# Peripherals.net
KiCad netlist of a schematic drawn in Altium Designer
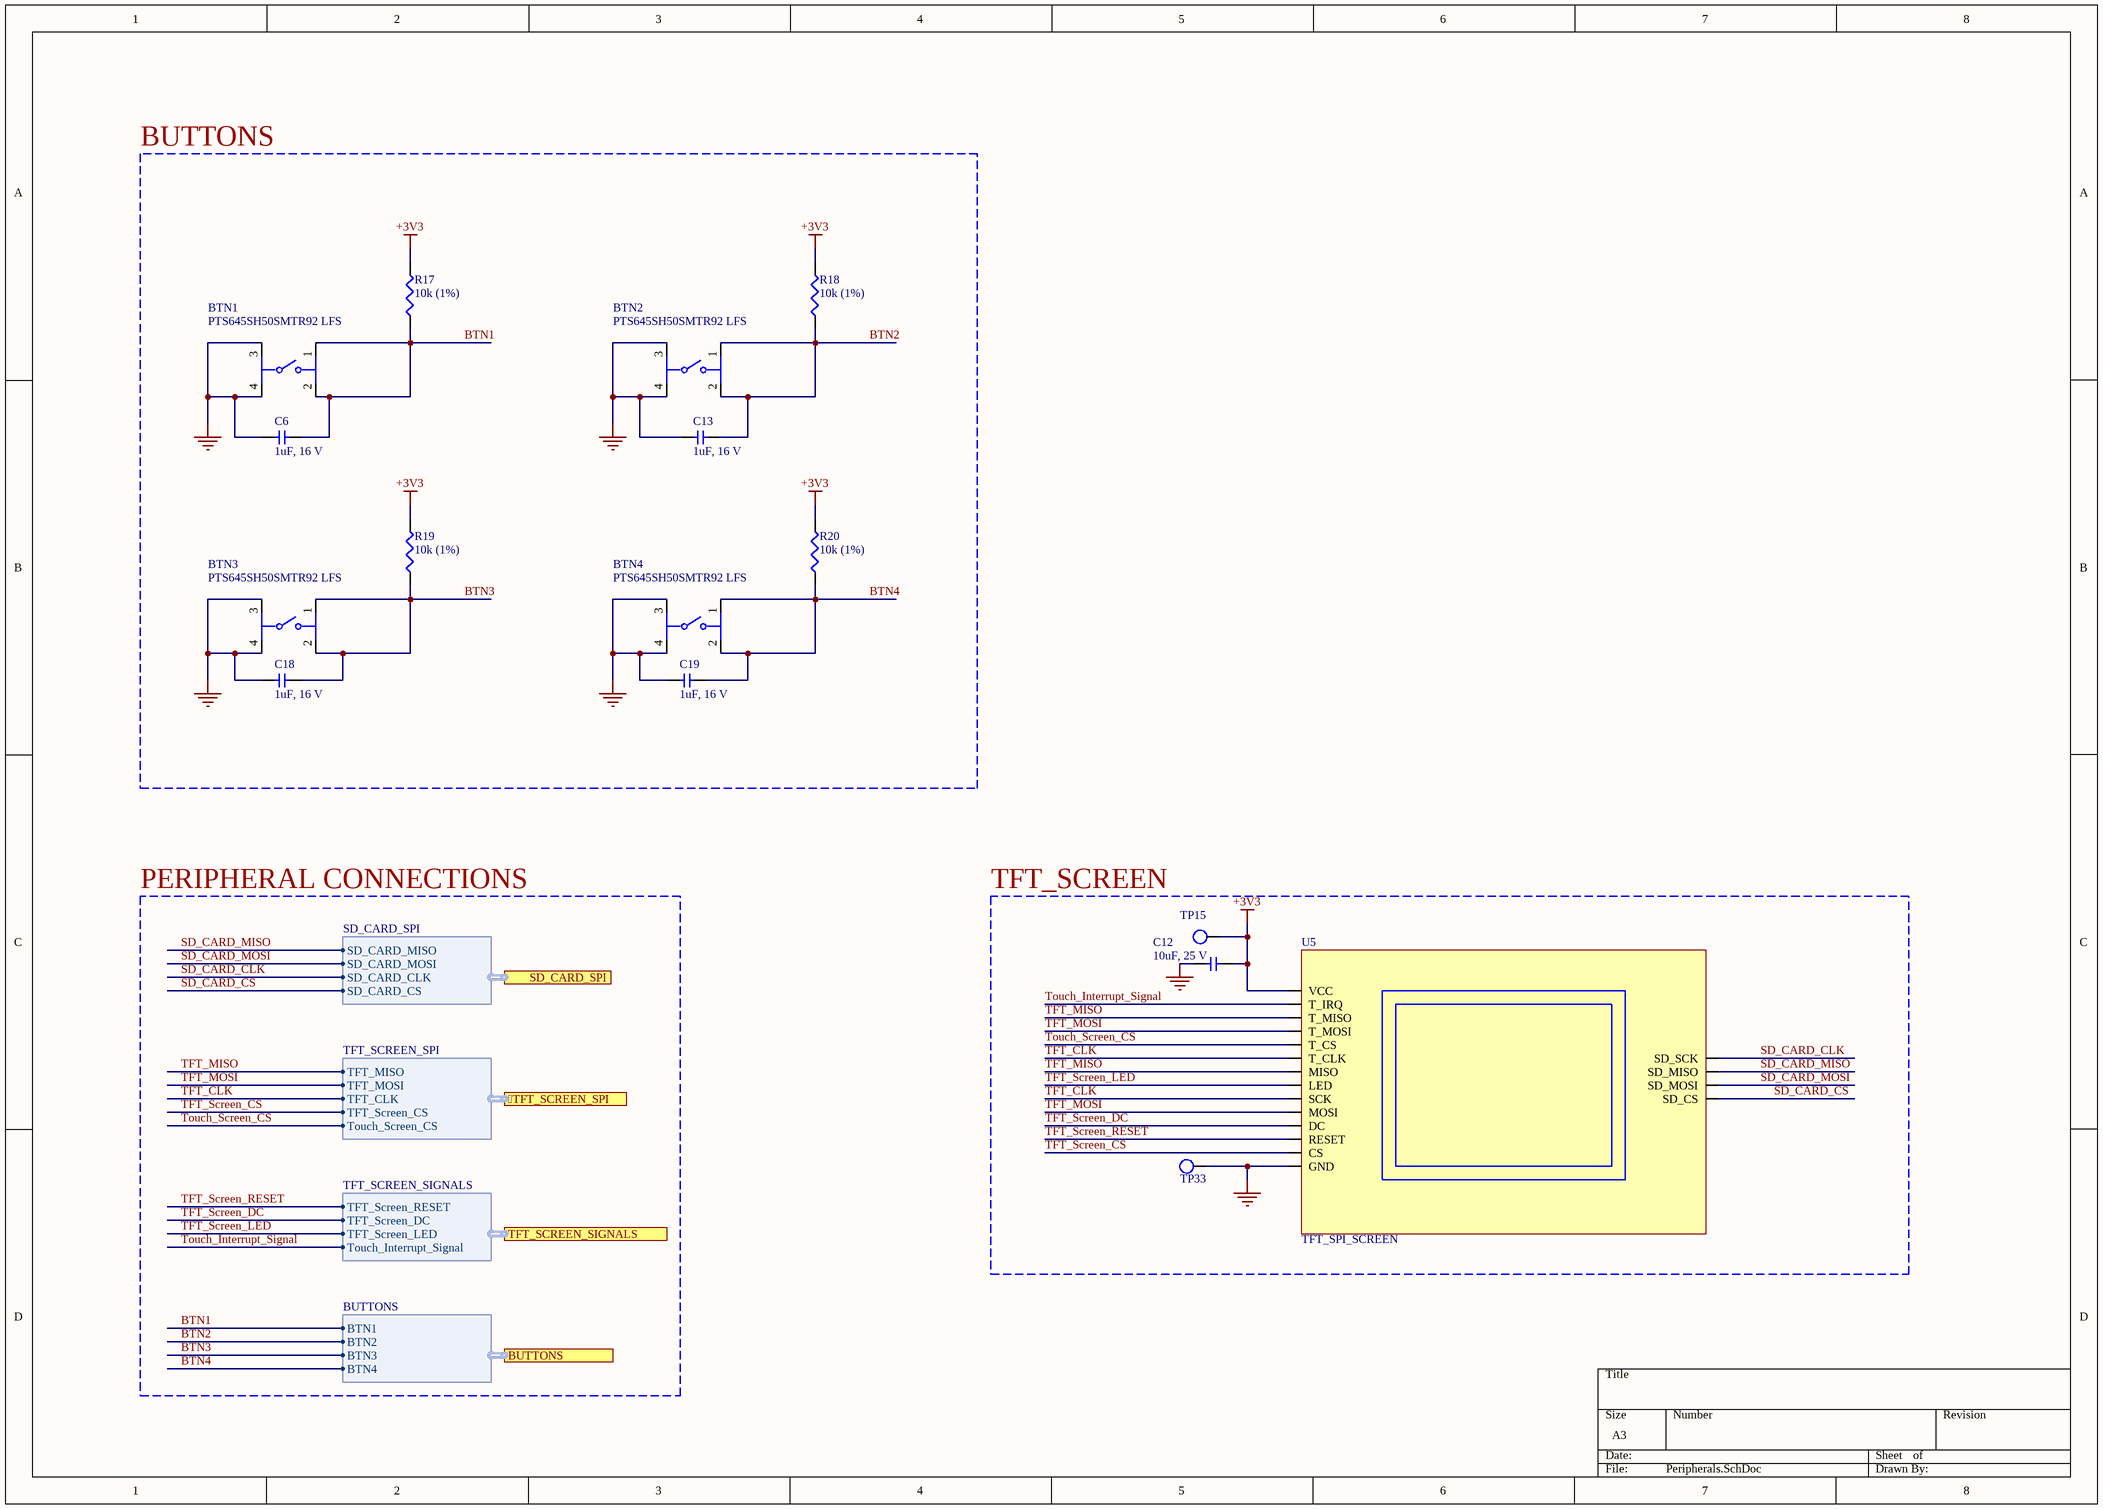
[diagram p0: Peripherals.SchDoc]

(export (version "E")
  (design (tool "Eeschema 10.0.6"))
  (components
    (comp (ref "BTN1")
      (value "PTS645SH50SMTR92 LFS")
      (footprint "FP-PTS645SH50SMTR92LFS-MFG")
      (description "Tactile Switch SPST-NO Top Actuated Surface Mount")
      (libsource (lib "SchLib") (part "PTS645SH50SMTR92 LFS"))
    )
    (comp (ref "BTN2")
      (value "PTS645SH50SMTR92 LFS")
      (footprint "FP-PTS645SH50SMTR92LFS-MFG")
      (description "Tactile Switch SPST-NO Top Actuated Surface Mount")
      (libsource (lib "SchLib") (part "PTS645SH50SMTR92 LFS"))
    )
    (comp (ref "BTN3")
      (value "PTS645SH50SMTR92 LFS")
      (footprint "FP-PTS645SH50SMTR92LFS-MFG")
      (description "Tactile Switch SPST-NO Top Actuated Surface Mount")
      (libsource (lib "SchLib") (part "PTS645SH50SMTR92 LFS"))
    )
    (comp (ref "BTN4")
      (value "PTS645SH50SMTR92 LFS")
      (footprint "FP-PTS645SH50SMTR92LFS-MFG")
      (description "Tactile Switch SPST-NO Top Actuated Surface Mount")
      (libsource (lib "SchLib") (part "PTS645SH50SMTR92 LFS"))
    )
    (comp (ref "C6")
      (value "1uF, 16 V")
      (footprint "0805_CAP")
      (libsource (lib "SchLib") (part "CL31B105KOFNNNE"))
    )
    (comp (ref "C12")
      (value "10uF, 25 V")
      (footprint "0805_CAP")
      (fields
        (field (name "MANUFACTURER") "Taiyo Yuden")
        (field (name "MANUFACTURER PART NUMBER") "TMK316BJ106KL-T")
      )
      (libsource (lib "SchLib") (part "TMK316BJ106KL-T"))
    )
    (comp (ref "C13")
      (value "1uF, 16 V")
      (footprint "0805_CAP")
      (libsource (lib "SchLib") (part "CL31B105KOFNNNE"))
    )
    (comp (ref "C18")
      (value "1uF, 16 V")
      (footprint "0805_CAP")
      (libsource (lib "SchLib") (part "CL31B105KOFNNNE"))
    )
    (comp (ref "C19")
      (value "1uF, 16 V")
      (footprint "0805_CAP")
      (libsource (lib "SchLib") (part "CL31B105KOFNNNE"))
    )
    (comp (ref "R17")
      (value "10k (1%)")
      (footprint "0805_Resistor")
      (fields (field (name "TOLERANCE") "1%"))
      (libsource (lib "SchLib") (part "RMCF0805FT10K0"))
    )
    (comp (ref "R18")
      (value "10k (1%)")
      (footprint "0805_Resistor")
      (fields (field (name "TOLERANCE") "1%"))
      (libsource (lib "SchLib") (part "RMCF0805FT10K0"))
    )
    (comp (ref "R19")
      (value "10k (1%)")
      (footprint "0805_Resistor")
      (fields (field (name "TOLERANCE") "1%"))
      (libsource (lib "SchLib") (part "RMCF0805FT10K0"))
    )
    (comp (ref "R20")
      (value "10k (1%)")
      (footprint "0805_Resistor")
      (fields (field (name "TOLERANCE") "1%"))
      (libsource (lib "SchLib") (part "RMCF0805FT10K0"))
    )
    (comp (ref "TP15")
      (value "Test Point")
      (footprint "Probe-Point")
      (description "Generic Test Point")
      (libsource (lib "University of Calgary Solar Car Team") (part "Test Point-Symbol-1"))
    )
    (comp (ref "TP33")
      (value "Test Point")
      (footprint "Probe-Point")
      (description "Generic Test Point")
      (libsource (lib "University of Calgary Solar Car Team") (part "Test Point-Symbol-1"))
    )
    (comp (ref "U5")
      (value "TFT_SPI_SCREEN")
      (footprint "TFT_SCREEN")
      (description "3.5inch SPI Module ILI9488 SKU:MSP3520")
      (libsource (lib "SchLib") (part "TFT_SPI_SCREEN"))
    )
  )
  (nets
    (net (code "5") (name "+3V3") (class "Default")
      (node (ref "C12") (pin "1") (pinfunction "1_1") (pintype "passive"))
      (node (ref "R17") (pin "2") (pinfunction "2_2") (pintype "passive"))
      (node (ref "R18") (pin "2") (pinfunction "2_2") (pintype "passive"))
      (node (ref "R19") (pin "2") (pinfunction "2_2") (pintype "passive"))
      (node (ref "R20") (pin "2") (pinfunction "2_2") (pintype "passive"))
      (node (ref "TP15") (pin "1") (pinfunction "1_1") (pintype "passive"))
      (node (ref "U5") (pin "1") (pinfunction "VCC_1") (pintype "passive"))
    )
    (net (code "6") (name "/BTN1") (class "Default")
      (node (ref "BTN1") (pin "1") (pinfunction "1_1") (pintype "passive"))
      (node (ref "BTN1") (pin "2") (pinfunction "2_2") (pintype "passive"))
      (node (ref "C6") (pin "2") (pinfunction "2_2") (pintype "passive"))
      (node (ref "R17") (pin "1") (pinfunction "1_1") (pintype "passive"))
    )
    (net (code "7") (name "/BTN2") (class "Default")
      (node (ref "BTN2") (pin "1") (pinfunction "1_1") (pintype "passive"))
      (node (ref "BTN2") (pin "2") (pinfunction "2_2") (pintype "passive"))
      (node (ref "C13") (pin "2") (pinfunction "2_2") (pintype "passive"))
      (node (ref "R18") (pin "1") (pinfunction "1_1") (pintype "passive"))
    )
    (net (code "8") (name "/BTN3") (class "Default")
      (node (ref "BTN3") (pin "1") (pinfunction "1_1") (pintype "passive"))
      (node (ref "BTN3") (pin "2") (pinfunction "2_2") (pintype "passive"))
      (node (ref "C18") (pin "2") (pinfunction "2_2") (pintype "passive"))
      (node (ref "R19") (pin "1") (pinfunction "1_1") (pintype "passive"))
    )
    (net (code "9") (name "/BTN4") (class "Default")
      (node (ref "BTN4") (pin "1") (pinfunction "1_1") (pintype "passive"))
      (node (ref "BTN4") (pin "2") (pinfunction "2_2") (pintype "passive"))
      (node (ref "C19") (pin "2") (pinfunction "2_2") (pintype "passive"))
      (node (ref "R20") (pin "1") (pinfunction "1_1") (pintype "passive"))
    )
    (net (code "10") (name "/SD_CARD_CLK") (class "Default")
      (node (ref "U5") (pin "18") (pinfunction "SD_SCK_18") (pintype "passive"))
    )
    (net (code "11") (name "/SD_CARD_CS") (class "Default")
      (node (ref "U5") (pin "15") (pinfunction "SD_CS_15") (pintype "passive"))
    )
    (net (code "12") (name "/SD_CARD_MISO") (class "Default")
      (node (ref "U5") (pin "17") (pinfunction "SD_MISO_17") (pintype "passive"))
    )
    (net (code "13") (name "/SD_CARD_MOSI") (class "Default")
      (node (ref "U5") (pin "16") (pinfunction "SD_MOSI_16") (pintype "passive"))
    )
    (net (code "14") (name "/TFT_CLK") (class "Default")
      (node (ref "U5") (pin "10") (pinfunction "T_CLK_10") (pintype "passive"))
      (node (ref "U5") (pin "7") (pinfunction "SCK_7") (pintype "passive"))
    )
    (net (code "15") (name "/TFT_MISO") (class "Default")
      (node (ref "U5") (pin "13") (pinfunction "T_MISO_13") (pintype "passive"))
      (node (ref "U5") (pin "9") (pinfunction "MISO_9") (pintype "passive"))
    )
    (net (code "16") (name "/TFT_MOSI") (class "Default")
      (node (ref "U5") (pin "12") (pinfunction "T_MOSI_12") (pintype "passive"))
      (node (ref "U5") (pin "6") (pinfunction "MOSI_6") (pintype "passive"))
    )
    (net (code "17") (name "/TFT_Screen_CS") (class "Default")
      (node (ref "U5") (pin "3") (pinfunction "CS_3") (pintype "passive"))
    )
    (net (code "18") (name "/TFT_Screen_DC") (class "Default")
      (node (ref "U5") (pin "5") (pinfunction "DC_5") (pintype "passive"))
    )
    (net (code "19") (name "/TFT_Screen_LED") (class "Default")
      (node (ref "U5") (pin "8") (pinfunction "LED_8") (pintype "passive"))
    )
    (net (code "20") (name "/TFT_Screen_RESET") (class "Default")
      (node (ref "U5") (pin "4") (pinfunction "RESET_4") (pintype "passive"))
    )
    (net (code "21") (name "/Touch_Interrupt_Signal") (class "Default")
      (node (ref "U5") (pin "14") (pinfunction "T_IRQ_14") (pintype "passive"))
    )
    (net (code "22") (name "/Touch_Screen_CS") (class "Default")
      (node (ref "U5") (pin "11") (pinfunction "T_CS_11") (pintype "passive"))
    )
    (net (code "27") (name "GND") (class "Default")
      (node (ref "BTN1") (pin "3") (pinfunction "3_3") (pintype "passive"))
      (node (ref "BTN1") (pin "4") (pinfunction "4_4") (pintype "passive"))
      (node (ref "BTN2") (pin "3") (pinfunction "3_3") (pintype "passive"))
      (node (ref "BTN2") (pin "4") (pinfunction "4_4") (pintype "passive"))
      (node (ref "BTN3") (pin "3") (pinfunction "3_3") (pintype "passive"))
      (node (ref "BTN3") (pin "4") (pinfunction "4_4") (pintype "passive"))
      (node (ref "BTN4") (pin "3") (pinfunction "3_3") (pintype "passive"))
      (node (ref "BTN4") (pin "4") (pinfunction "4_4") (pintype "passive"))
      (node (ref "C12") (pin "2") (pinfunction "2_2") (pintype "passive"))
      (node (ref "C13") (pin "1") (pinfunction "1_1") (pintype "passive"))
      (node (ref "C18") (pin "1") (pinfunction "1_1") (pintype "passive"))
      (node (ref "C19") (pin "1") (pinfunction "1_1") (pintype "passive"))
      (node (ref "C6") (pin "1") (pinfunction "1_1") (pintype "passive"))
      (node (ref "TP33") (pin "1") (pinfunction "1_1") (pintype "passive"))
      (node (ref "U5") (pin "2") (pinfunction "GND_2") (pintype "passive"))
    )
  )
)
